# Project.net
KiCad netlist of a schematic drawn in EAGLE
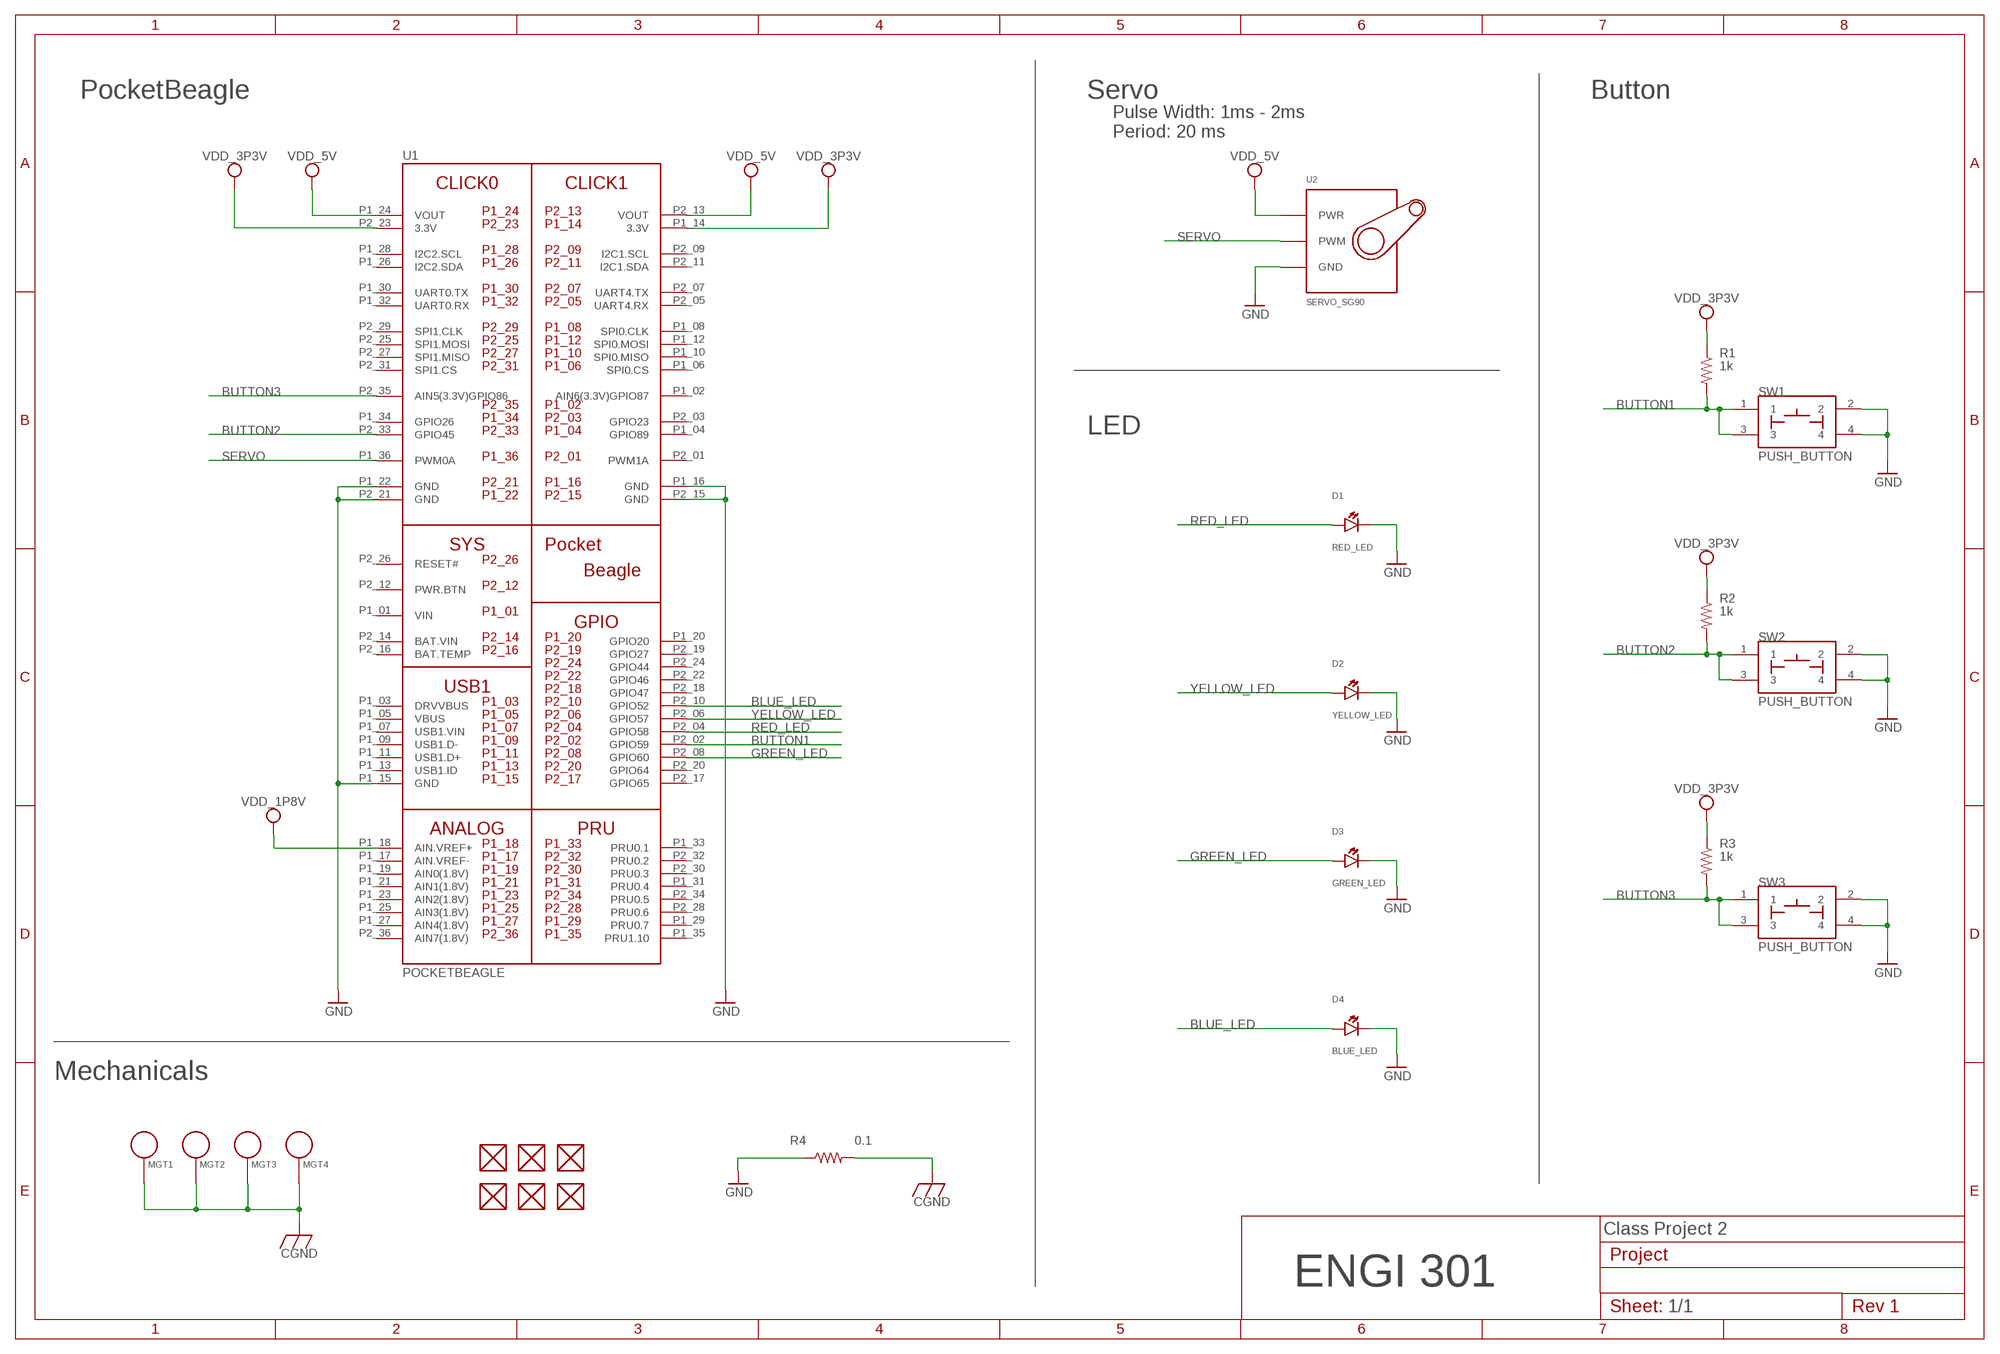
[diagram p0: schematic, sheet 1]

(export (version "E")
  (design (tool "Eeschema 10.0.6"))
  (components
    (comp (ref "D1")
      (value "RED_LED")
      (footprint "eagle-import:EIA-STD")
      (libsource (lib "eagle-import") (part "LED"))
    )
    (comp (ref "D2")
      (value "YELLOW_LED")
      (footprint "eagle-import:EIA-STD")
      (libsource (lib "eagle-import") (part "LED"))
    )
    (comp (ref "D3")
      (value "GREEN_LED")
      (footprint "eagle-import:EIA-STD")
      (libsource (lib "eagle-import") (part "LED"))
    )
    (comp (ref "D4")
      (value "BLUE_LED")
      (footprint "eagle-import:EIA-STD")
      (libsource (lib "eagle-import") (part "LED"))
    )
    (comp (ref "FUD1")
      (value "FIDUCIAL")
      (footprint "eagle-import:FIDUCIAL_40MIL")
      (libsource (lib "eagle-import") (part "FIDUCIAL"))
    )
    (comp (ref "FUD2")
      (value "FIDUCIAL")
      (footprint "eagle-import:FIDUCIAL_40MIL")
      (libsource (lib "eagle-import") (part "FIDUCIAL"))
    )
    (comp (ref "FUD3")
      (value "FIDUCIAL")
      (footprint "eagle-import:FIDUCIAL_40MIL")
      (libsource (lib "eagle-import") (part "FIDUCIAL"))
    )
    (comp (ref "FUD4")
      (value "FIDUCIAL")
      (footprint "eagle-import:FIDUCIAL_40MIL")
      (libsource (lib "eagle-import") (part "FIDUCIAL"))
    )
    (comp (ref "FUD5")
      (value "FIDUCIAL")
      (footprint "eagle-import:FIDUCIAL_40MIL")
      (libsource (lib "eagle-import") (part "FIDUCIAL"))
    )
    (comp (ref "FUD6")
      (value "FIDUCIAL")
      (footprint "eagle-import:FIDUCIAL_40MIL")
      (libsource (lib "eagle-import") (part "FIDUCIAL"))
    )
    (comp (ref "MGT1")
      (value "MOUNTING_HOLE")
      (footprint "eagle-import:MOUNTING_HOLE")
      (libsource (lib "eagle-import") (part "MOUNTING_HOLE"))
    )
    (comp (ref "MGT2")
      (value "MOUNTING_HOLE")
      (footprint "eagle-import:MOUNTING_HOLE")
      (libsource (lib "eagle-import") (part "MOUNTING_HOLE"))
    )
    (comp (ref "MGT3")
      (value "MOUNTING_HOLE")
      (footprint "eagle-import:MOUNTING_HOLE")
      (libsource (lib "eagle-import") (part "MOUNTING_HOLE"))
    )
    (comp (ref "MGT4")
      (value "MOUNTING_HOLE")
      (footprint "eagle-import:MOUNTING_HOLE")
      (libsource (lib "eagle-import") (part "MOUNTING_HOLE"))
    )
    (comp (ref "R1")
      (value "1k")
      (footprint "eagle-import:R0603")
      (libsource (lib "eagle-import") (part "R_R0603"))
    )
    (comp (ref "R2")
      (value "1k")
      (footprint "eagle-import:R0603")
      (libsource (lib "eagle-import") (part "R_R0603"))
    )
    (comp (ref "R3")
      (value "1k")
      (footprint "eagle-import:R0603")
      (libsource (lib "eagle-import") (part "R_R0603"))
    )
    (comp (ref "R4")
      (value "0.1")
      (footprint "eagle-import:R0805")
      (libsource (lib "eagle-import") (part "R_R0805"))
    )
    (comp (ref "SW1")
      (value "PUSH_BUTTON")
      (footprint "eagle-import:BUTTON_12.5MM")
      (libsource (lib "eagle-import") (part "PUSH_BUTTON"))
    )
    (comp (ref "SW2")
      (value "PUSH_BUTTON")
      (footprint "eagle-import:BUTTON_12.5MM")
      (libsource (lib "eagle-import") (part "PUSH_BUTTON"))
    )
    (comp (ref "SW3")
      (value "PUSH_BUTTON")
      (footprint "eagle-import:BUTTON_12.5MM")
      (libsource (lib "eagle-import") (part "PUSH_BUTTON"))
    )
    (comp (ref "U1")
      (value "POCKETBEAGLE")
      (footprint "eagle-import:POCKETBEAGLE")
      (libsource (lib "eagle-import") (part "POCKETBEAGLE"))
    )
    (comp (ref "U2")
      (value "SERVO_SG90")
      (footprint "eagle-import:SERVO-X1")
      (libsource (lib "eagle-import") (part "SERVO_SG90"))
    )
  )
  (nets
    (net (code "1") (name "/BAT.VIN") (class "Default")
      (node (ref "U1") (pin "P2_14") (pinfunction "BAT.VIN_P2_14") (pintype "power_in"))
    )
    (net (code "2") (name "/BLUE_LED") (class "Default")
      (node (ref "D4") (pin "ANODE") (pinfunction "ANODE_ANODE") (pintype "bidirectional"))
      (node (ref "U1") (pin "P2_10") (pinfunction "GPIO52_P2_10") (pintype "bidirectional"))
    )
    (net (code "3") (name "/BUTTON1") (class "Default")
      (node (ref "R1") (pin "2") (pinfunction "2_2") (pintype "passive"))
      (node (ref "SW1") (pin "1") (pinfunction "1_1") (pintype "bidirectional"))
      (node (ref "SW1") (pin "3") (pinfunction "3_3") (pintype "bidirectional"))
      (node (ref "U1") (pin "P2_02") (pinfunction "GPIO59_P2_02") (pintype "bidirectional"))
    )
    (net (code "4") (name "/BUTTON2") (class "Default")
      (node (ref "R2") (pin "2") (pinfunction "2_2") (pintype "passive"))
      (node (ref "SW2") (pin "1") (pinfunction "1_1") (pintype "bidirectional"))
      (node (ref "SW2") (pin "3") (pinfunction "3_3") (pintype "bidirectional"))
      (node (ref "U1") (pin "P2_33") (pinfunction "GPIO45_P2_33") (pintype "bidirectional"))
    )
    (net (code "5") (name "/BUTTON3") (class "Default")
      (node (ref "R3") (pin "2") (pinfunction "2_2") (pintype "passive"))
      (node (ref "SW3") (pin "1") (pinfunction "1_1") (pintype "bidirectional"))
      (node (ref "SW3") (pin "3") (pinfunction "3_3") (pintype "bidirectional"))
      (node (ref "U1") (pin "P2_35") (pinfunction "AIN5(3.3V)GPIO86_P2_35") (pintype "bidirectional"))
    )
    (net (code "6") (name "/GREEN_LED") (class "Default")
      (node (ref "D3") (pin "ANODE") (pinfunction "ANODE_ANODE") (pintype "bidirectional"))
      (node (ref "U1") (pin "P2_08") (pinfunction "GPIO60_P2_08") (pintype "bidirectional"))
    )
    (net (code "7") (name "/RED_LED") (class "Default")
      (node (ref "D1") (pin "ANODE") (pinfunction "ANODE_ANODE") (pintype "bidirectional"))
      (node (ref "U1") (pin "P2_04") (pinfunction "GPIO58_P2_04") (pintype "bidirectional"))
    )
    (net (code "8") (name "/SERVO") (class "Default")
      (node (ref "U1") (pin "P1_36") (pinfunction "PWM0A_P1_36") (pintype "bidirectional"))
      (node (ref "U2") (pin "SIG") (pinfunction "PWM_SIG") (pintype "bidirectional"))
    )
    (net (code "9") (name "/VIN") (class "Default")
      (node (ref "U1") (pin "P1_01") (pinfunction "VIN_P1_01") (pintype "power_in"))
    )
    (net (code "10") (name "/YELLOW_LED") (class "Default")
      (node (ref "D2") (pin "ANODE") (pinfunction "ANODE_ANODE") (pintype "bidirectional"))
      (node (ref "U1") (pin "P2_06") (pinfunction "GPIO57_P2_06") (pintype "bidirectional"))
    )
    (net (code "11") (name "CGND") (class "Default")
      (node (ref "MGT1") (pin "P$1") (pinfunction "P$1_P$1") (pintype "bidirectional"))
      (node (ref "MGT2") (pin "P$1") (pinfunction "P$1_P$1") (pintype "bidirectional"))
      (node (ref "MGT3") (pin "P$1") (pinfunction "P$1_P$1") (pintype "bidirectional"))
      (node (ref "MGT4") (pin "P$1") (pinfunction "P$1_P$1") (pintype "bidirectional"))
      (node (ref "R4") (pin "2") (pinfunction "2_2") (pintype "passive"))
    )
    (net (code "12") (name "GND") (class "Default")
      (node (ref "D1") (pin "CATHODE") (pinfunction "CATHODE_CATHODE") (pintype "bidirectional"))
      (node (ref "D2") (pin "CATHODE") (pinfunction "CATHODE_CATHODE") (pintype "bidirectional"))
      (node (ref "D3") (pin "CATHODE") (pinfunction "CATHODE_CATHODE") (pintype "bidirectional"))
      (node (ref "D4") (pin "CATHODE") (pinfunction "CATHODE_CATHODE") (pintype "bidirectional"))
      (node (ref "R4") (pin "1") (pinfunction "1_1") (pintype "passive"))
      (node (ref "SW1") (pin "2") (pinfunction "2_2") (pintype "bidirectional"))
      (node (ref "SW1") (pin "4") (pinfunction "4_4") (pintype "bidirectional"))
      (node (ref "SW2") (pin "2") (pinfunction "2_2") (pintype "bidirectional"))
      (node (ref "SW2") (pin "4") (pinfunction "4_4") (pintype "bidirectional"))
      (node (ref "SW3") (pin "2") (pinfunction "2_2") (pintype "bidirectional"))
      (node (ref "SW3") (pin "4") (pinfunction "4_4") (pintype "bidirectional"))
      (node (ref "U1") (pin "P1_15") (pinfunction "GND_P1_15") (pintype "bidirectional"))
      (node (ref "U1") (pin "P1_16") (pinfunction "GND_P1_16") (pintype "power_in"))
      (node (ref "U1") (pin "P1_22") (pinfunction "GND_P1_22") (pintype "power_in"))
      (node (ref "U1") (pin "P2_15") (pinfunction "GND_P2_15") (pintype "power_in"))
      (node (ref "U1") (pin "P2_21") (pinfunction "GND_P2_21") (pintype "power_in"))
      (node (ref "U2") (pin "GND") (pinfunction "GND_GND") (pintype "bidirectional"))
    )
    (net (code "13") (name "VDD_1P8V") (class "Default")
      (node (ref "U1") (pin "P1_18") (pinfunction "AIN.VREF+_P1_18") (pintype "input"))
    )
    (net (code "14") (name "VDD_3P3V") (class "Default")
      (node (ref "R1") (pin "1") (pinfunction "1_1") (pintype "passive"))
      (node (ref "R2") (pin "1") (pinfunction "1_1") (pintype "passive"))
      (node (ref "R3") (pin "1") (pinfunction "1_1") (pintype "passive"))
      (node (ref "U1") (pin "P1_14") (pinfunction "3.3V_P1_14") (pintype "power_in"))
      (node (ref "U1") (pin "P2_23") (pinfunction "3.3V_P2_23") (pintype "power_in"))
    )
    (net (code "15") (name "VDD_5V") (class "Default")
      (node (ref "U1") (pin "P1_24") (pinfunction "VOUT_P1_24") (pintype "power_in"))
      (node (ref "U1") (pin "P2_13") (pinfunction "VOUT_P2_13") (pintype "power_in"))
      (node (ref "U2") (pin "PWR") (pinfunction "PWR_PWR") (pintype "bidirectional"))
    )
    (net (code "16") (name "unconnected-(FUD1-PadP$1)") (class "Default")
      (node (ref "FUD1") (pin "P$1") (pinfunction "P$1_P$1") (pintype "no_connect"))
    )
    (net (code "17") (name "unconnected-(FUD2-PadP$1)") (class "Default")
      (node (ref "FUD2") (pin "P$1") (pinfunction "P$1_P$1") (pintype "no_connect"))
    )
    (net (code "18") (name "unconnected-(FUD3-PadP$1)") (class "Default")
      (node (ref "FUD3") (pin "P$1") (pinfunction "P$1_P$1") (pintype "no_connect"))
    )
    (net (code "19") (name "unconnected-(FUD4-PadP$1)") (class "Default")
      (node (ref "FUD4") (pin "P$1") (pinfunction "P$1_P$1") (pintype "no_connect"))
    )
    (net (code "20") (name "unconnected-(FUD5-PadP$1)") (class "Default")
      (node (ref "FUD5") (pin "P$1") (pinfunction "P$1_P$1") (pintype "no_connect"))
    )
    (net (code "21") (name "unconnected-(FUD6-PadP$1)") (class "Default")
      (node (ref "FUD6") (pin "P$1") (pinfunction "P$1_P$1") (pintype "no_connect"))
    )
    (net (code "22") (name "unconnected-(U1-AIN.VREF--PadP1_17)") (class "Default")
      (node (ref "U1") (pin "P1_17") (pinfunction "AIN.VREF-_P1_17") (pintype "input"))
    )
    (net (code "23") (name "unconnected-(U1-AIN0(1.8V)-PadP1_19)") (class "Default")
      (node (ref "U1") (pin "P1_19") (pinfunction "AIN0(1.8V)_P1_19") (pintype "input"))
    )
    (net (code "24") (name "unconnected-(U1-AIN1(1.8V)-PadP1_21)") (class "Default")
      (node (ref "U1") (pin "P1_21") (pinfunction "AIN1(1.8V)_P1_21") (pintype "input"))
    )
    (net (code "25") (name "unconnected-(U1-AIN2(1.8V)-PadP1_23)") (class "Default")
      (node (ref "U1") (pin "P1_23") (pinfunction "AIN2(1.8V)_P1_23") (pintype "input"))
    )
    (net (code "26") (name "unconnected-(U1-AIN3(1.8V)-PadP1_25)") (class "Default")
      (node (ref "U1") (pin "P1_25") (pinfunction "AIN3(1.8V)_P1_25") (pintype "input"))
    )
    (net (code "27") (name "unconnected-(U1-AIN4(1.8V)-PadP1_27)") (class "Default")
      (node (ref "U1") (pin "P1_27") (pinfunction "AIN4(1.8V)_P1_27") (pintype "input"))
    )
    (net (code "28") (name "unconnected-(U1-AIN6(3.3V)GPIO87-PadP1_02)") (class "Default")
      (node (ref "U1") (pin "P1_02") (pinfunction "AIN6(3.3V)GPIO87_P1_02") (pintype "bidirectional"))
    )
    (net (code "29") (name "unconnected-(U1-AIN7(1.8V)-PadP2_36)") (class "Default")
      (node (ref "U1") (pin "P2_36") (pinfunction "AIN7(1.8V)_P2_36") (pintype "input"))
    )
    (net (code "30") (name "unconnected-(U1-BAT.TEMP-PadP2_16)") (class "Default")
      (node (ref "U1") (pin "P2_16") (pinfunction "BAT.TEMP_P2_16") (pintype "input"))
    )
    (net (code "31") (name "unconnected-(U1-DRVVBUS-PadP1_03)") (class "Default")
      (node (ref "U1") (pin "P1_03") (pinfunction "DRVVBUS_P1_03") (pintype "bidirectional"))
    )
    (net (code "32") (name "unconnected-(U1-GPIO20-PadP1_20)") (class "Default")
      (node (ref "U1") (pin "P1_20") (pinfunction "GPIO20_P1_20") (pintype "bidirectional"))
    )
    (net (code "33") (name "unconnected-(U1-GPIO23-PadP2_03)") (class "Default")
      (node (ref "U1") (pin "P2_03") (pinfunction "GPIO23_P2_03") (pintype "bidirectional"))
    )
    (net (code "34") (name "unconnected-(U1-GPIO26-PadP1_34)") (class "Default")
      (node (ref "U1") (pin "P1_34") (pinfunction "GPIO26_P1_34") (pintype "bidirectional"))
    )
    (net (code "35") (name "unconnected-(U1-GPIO27-PadP2_19)") (class "Default")
      (node (ref "U1") (pin "P2_19") (pinfunction "GPIO27_P2_19") (pintype "bidirectional"))
    )
    (net (code "36") (name "unconnected-(U1-GPIO44-PadP2_24)") (class "Default")
      (node (ref "U1") (pin "P2_24") (pinfunction "GPIO44_P2_24") (pintype "bidirectional"))
    )
    (net (code "37") (name "unconnected-(U1-GPIO46-PadP2_22)") (class "Default")
      (node (ref "U1") (pin "P2_22") (pinfunction "GPIO46_P2_22") (pintype "bidirectional"))
    )
    (net (code "38") (name "unconnected-(U1-GPIO47-PadP2_18)") (class "Default")
      (node (ref "U1") (pin "P2_18") (pinfunction "GPIO47_P2_18") (pintype "bidirectional"))
    )
    (net (code "39") (name "unconnected-(U1-GPIO64-PadP2_20)") (class "Default")
      (node (ref "U1") (pin "P2_20") (pinfunction "GPIO64_P2_20") (pintype "bidirectional"))
    )
    (net (code "40") (name "unconnected-(U1-GPIO65-PadP2_17)") (class "Default")
      (node (ref "U1") (pin "P2_17") (pinfunction "GPIO65_P2_17") (pintype "bidirectional"))
    )
    (net (code "41") (name "unconnected-(U1-GPIO89-PadP1_04)") (class "Default")
      (node (ref "U1") (pin "P1_04") (pinfunction "GPIO89_P1_04") (pintype "bidirectional"))
    )
    (net (code "42") (name "unconnected-(U1-I2C1.SCL-PadP2_09)") (class "Default")
      (node (ref "U1") (pin "P2_09") (pinfunction "I2C1.SCL_P2_09") (pintype "bidirectional"))
    )
    (net (code "43") (name "unconnected-(U1-I2C1.SDA-PadP2_11)") (class "Default")
      (node (ref "U1") (pin "P2_11") (pinfunction "I2C1.SDA_P2_11") (pintype "bidirectional"))
    )
    (net (code "44") (name "unconnected-(U1-I2C2.SCL-PadP1_28)") (class "Default")
      (node (ref "U1") (pin "P1_28") (pinfunction "I2C2.SCL_P1_28") (pintype "bidirectional"))
    )
    (net (code "45") (name "unconnected-(U1-I2C2.SDA-PadP1_26)") (class "Default")
      (node (ref "U1") (pin "P1_26") (pinfunction "I2C2.SDA_P1_26") (pintype "bidirectional"))
    )
    (net (code "46") (name "unconnected-(U1-PRU0.1-PadP1_33)") (class "Default")
      (node (ref "U1") (pin "P1_33") (pinfunction "PRU0.1_P1_33") (pintype "bidirectional"))
    )
    (net (code "47") (name "unconnected-(U1-PRU0.2-PadP2_32)") (class "Default")
      (node (ref "U1") (pin "P2_32") (pinfunction "PRU0.2_P2_32") (pintype "bidirectional"))
    )
    (net (code "48") (name "unconnected-(U1-PRU0.3-PadP2_30)") (class "Default")
      (node (ref "U1") (pin "P2_30") (pinfunction "PRU0.3_P2_30") (pintype "bidirectional"))
    )
    (net (code "49") (name "unconnected-(U1-PRU0.4-PadP1_31)") (class "Default")
      (node (ref "U1") (pin "P1_31") (pinfunction "PRU0.4_P1_31") (pintype "bidirectional"))
    )
    (net (code "50") (name "unconnected-(U1-PRU0.5-PadP2_34)") (class "Default")
      (node (ref "U1") (pin "P2_34") (pinfunction "PRU0.5_P2_34") (pintype "bidirectional"))
    )
    (net (code "51") (name "unconnected-(U1-PRU0.6-PadP2_28)") (class "Default")
      (node (ref "U1") (pin "P2_28") (pinfunction "PRU0.6_P2_28") (pintype "bidirectional"))
    )
    (net (code "52") (name "unconnected-(U1-PRU0.7-PadP1_29)") (class "Default")
      (node (ref "U1") (pin "P1_29") (pinfunction "PRU0.7_P1_29") (pintype "bidirectional"))
    )
    (net (code "53") (name "unconnected-(U1-PRU1.10-PadP1_35)") (class "Default")
      (node (ref "U1") (pin "P1_35") (pinfunction "PRU1.10_P1_35") (pintype "bidirectional"))
    )
    (net (code "54") (name "unconnected-(U1-PWM1A-PadP2_01)") (class "Default")
      (node (ref "U1") (pin "P2_01") (pinfunction "PWM1A_P2_01") (pintype "bidirectional"))
    )
    (net (code "55") (name "unconnected-(U1-PWR.BTN-PadP2_12)") (class "Default")
      (node (ref "U1") (pin "P2_12") (pinfunction "PWR.BTN_P2_12") (pintype "input"))
    )
    (net (code "56") (name "unconnected-(U1-RESET#-PadP2_26)") (class "Default")
      (node (ref "U1") (pin "P2_26") (pinfunction "RESET#_P2_26") (pintype "input"))
    )
    (net (code "57") (name "unconnected-(U1-SPI0.CLK-PadP1_08)") (class "Default")
      (node (ref "U1") (pin "P1_08") (pinfunction "SPI0.CLK_P1_08") (pintype "bidirectional"))
    )
    (net (code "58") (name "unconnected-(U1-SPI0.CS-PadP1_06)") (class "Default")
      (node (ref "U1") (pin "P1_06") (pinfunction "SPI0.CS_P1_06") (pintype "bidirectional"))
    )
    (net (code "59") (name "unconnected-(U1-SPI0.MISO-PadP1_10)") (class "Default")
      (node (ref "U1") (pin "P1_10") (pinfunction "SPI0.MISO_P1_10") (pintype "bidirectional"))
    )
    (net (code "60") (name "unconnected-(U1-SPI0.MOSI-PadP1_12)") (class "Default")
      (node (ref "U1") (pin "P1_12") (pinfunction "SPI0.MOSI_P1_12") (pintype "bidirectional"))
    )
    (net (code "61") (name "unconnected-(U1-SPI1.CLK-PadP2_29)") (class "Default")
      (node (ref "U1") (pin "P2_29") (pinfunction "SPI1.CLK_P2_29") (pintype "bidirectional"))
    )
    (net (code "62") (name "unconnected-(U1-SPI1.CS-PadP2_31)") (class "Default")
      (node (ref "U1") (pin "P2_31") (pinfunction "SPI1.CS_P2_31") (pintype "bidirectional"))
    )
    (net (code "63") (name "unconnected-(U1-SPI1.MISO-PadP2_27)") (class "Default")
      (node (ref "U1") (pin "P2_27") (pinfunction "SPI1.MISO_P2_27") (pintype "bidirectional"))
    )
    (net (code "64") (name "unconnected-(U1-SPI1.MOSI-PadP2_25)") (class "Default")
      (node (ref "U1") (pin "P2_25") (pinfunction "SPI1.MOSI_P2_25") (pintype "bidirectional"))
    )
    (net (code "65") (name "unconnected-(U1-UART0.RX-PadP1_32)") (class "Default")
      (node (ref "U1") (pin "P1_32") (pinfunction "UART0.RX_P1_32") (pintype "bidirectional"))
    )
    (net (code "66") (name "unconnected-(U1-UART0.TX-PadP1_30)") (class "Default")
      (node (ref "U1") (pin "P1_30") (pinfunction "UART0.TX_P1_30") (pintype "bidirectional"))
    )
    (net (code "67") (name "unconnected-(U1-UART4.RX-PadP2_05)") (class "Default")
      (node (ref "U1") (pin "P2_05") (pinfunction "UART4.RX_P2_05") (pintype "bidirectional"))
    )
    (net (code "68") (name "unconnected-(U1-UART4.TX-PadP2_07)") (class "Default")
      (node (ref "U1") (pin "P2_07") (pinfunction "UART4.TX_P2_07") (pintype "bidirectional"))
    )
    (net (code "69") (name "unconnected-(U1-USB1.D+-PadP1_11)") (class "Default")
      (node (ref "U1") (pin "P1_11") (pinfunction "USB1.D+_P1_11") (pintype "bidirectional"))
    )
    (net (code "70") (name "unconnected-(U1-USB1.D--PadP1_09)") (class "Default")
      (node (ref "U1") (pin "P1_09") (pinfunction "USB1.D-_P1_09") (pintype "bidirectional"))
    )
    (net (code "71") (name "unconnected-(U1-USB1.ID-PadP1_13)") (class "Default")
      (node (ref "U1") (pin "P1_13") (pinfunction "USB1.ID_P1_13") (pintype "bidirectional"))
    )
    (net (code "72") (name "unconnected-(U1-USB1.VIN-PadP1_07)") (class "Default")
      (node (ref "U1") (pin "P1_07") (pinfunction "USB1.VIN_P1_07") (pintype "bidirectional"))
    )
    (net (code "73") (name "unconnected-(U1-VBUS-PadP1_05)") (class "Default")
      (node (ref "U1") (pin "P1_05") (pinfunction "VBUS_P1_05") (pintype "bidirectional"))
    )
  )
)
